# clapclap1386.net
KiCad netlist of a schematic drawn in EAGLE
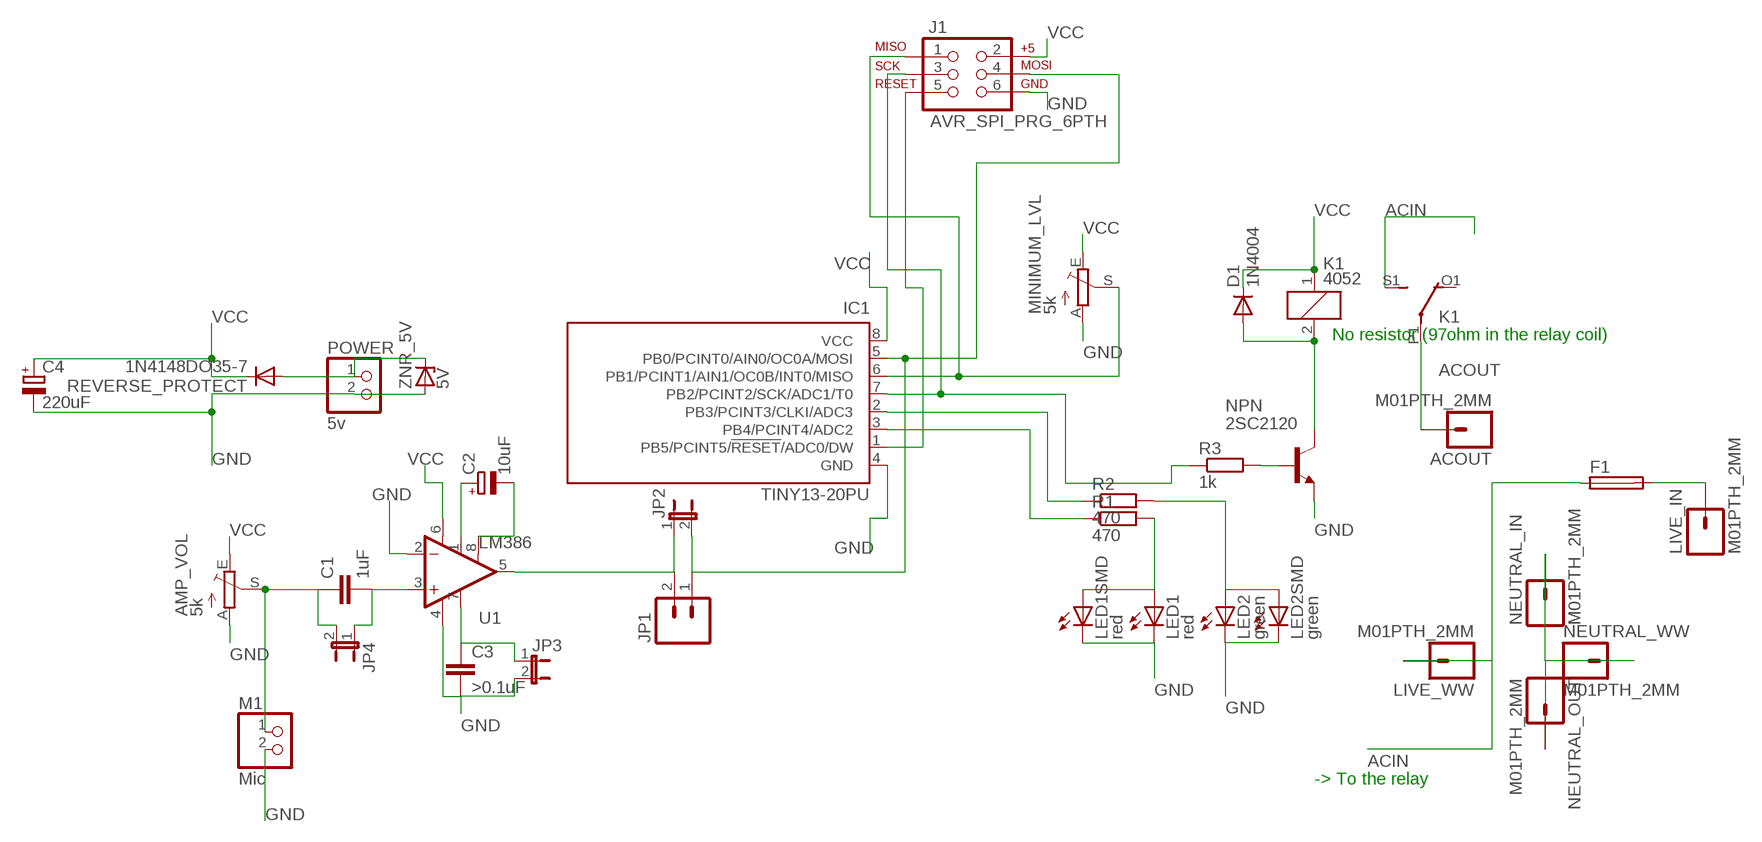
[diagram p0: schematic, sheet 1]

(export (version "E")
  (design (tool "Eeschema 10.0.6"))
  (components
    (comp (ref "ACOUT")
      (value "M01PTH_2MM")
      (footprint "eagle-import:1X01_2MM")
      (libsource (lib "eagle-import") (part "M01PTH_2MM"))
    )
    (comp (ref "AMP_VOL")
      (value "5k")
      (footprint "eagle-import:CT6")
      (libsource (lib "eagle-import") (part "TRIM_EU-CT6"))
    )
    (comp (ref "C1")
      (value "1uF")
      (footprint "eagle-import:C050-024X044")
      (libsource (lib "eagle-import") (part "C-EU050-024X044"))
    )
    (comp (ref "C2")
      (value "10uF")
      (footprint "eagle-import:E2,5-6E")
      (libsource (lib "eagle-import") (part "resistor_CPOL-EUE2,5-6E"))
    )
    (comp (ref "C3")
      (value ">0.1uF")
      (footprint "eagle-import:C025-025X050")
      (libsource (lib "eagle-import") (part "C-EU025-025X050"))
    )
    (comp (ref "C4")
      (value "220uF")
      (footprint "eagle-import:E2,5-6E")
      (libsource (lib "eagle-import") (part "CPOL-EUE2,5-6E"))
    )
    (comp (ref "D1")
      (value "1N4004")
      (footprint "eagle-import:DO41-10")
      (libsource (lib "eagle-import") (part "1N4004"))
    )
    (comp (ref "F1")
      (value "TE5")
      (footprint "eagle-import:TE5")
      (libsource (lib "eagle-import") (part "TE5"))
    )
    (comp (ref "IC1")
      (value "TINY13-20PU")
      (footprint "eagle-import:DIL08")
      (fields (field (name "MPN") "ATTINY13-20PU"))
      (libsource (lib "eagle-import") (part "TINY13PU-20"))
    )
    (comp (ref "J1")
      (value "AVR_SPI_PRG_6PTH")
      (footprint "eagle-import:2X3")
      (libsource (lib "eagle-import") (part "AVR_SPI_PRG_6PTH"))
    )
    (comp (ref "JP1")
      (value "M02PTH")
      (footprint "eagle-import:1X02")
      (libsource (lib "eagle-import") (part "M02PTH"))
    )
    (comp (ref "JP2")
      (value "JUMPER-2SMD-NO")
      (footprint "eagle-import:SJ_2S-NO")
      (libsource (lib "eagle-import") (part "JUMPER-2SMD-NO"))
    )
    (comp (ref "JP3")
      (value "JUMPER-2SMD-NO")
      (footprint "eagle-import:SJ_2S-NO")
      (libsource (lib "eagle-import") (part "JUMPER-2SMD-NO"))
    )
    (comp (ref "JP4")
      (value "JUMPER-2SMD-NO")
      (footprint "eagle-import:SJ_2S-NO")
      (libsource (lib "eagle-import") (part "JUMPER-2SMD-NO"))
    )
    (comp (ref "K1")
      (value "4052")
      (footprint "eagle-import:F4052")
      (libsource (lib "eagle-import") (part "4052"))
    )
    (comp (ref "LED1")
      (value "red")
      (footprint "eagle-import:LED3MM")
      (libsource (lib "eagle-import") (part "LED3MM"))
    )
    (comp (ref "LED1SMD")
      (value "red")
      (footprint "eagle-import:KA-3528ASYC")
      (libsource (lib "eagle-import") (part "LEDKA-3528ASYC"))
    )
    (comp (ref "LED2")
      (value "green")
      (footprint "eagle-import:LED3MM")
      (libsource (lib "eagle-import") (part "LED3MM"))
    )
    (comp (ref "LED2SMD")
      (value "green")
      (footprint "eagle-import:KA-3528ASYC")
      (libsource (lib "eagle-import") (part "LEDKA-3528ASYC"))
    )
    (comp (ref "LIVE_IN")
      (value "M01PTH_2MM")
      (footprint "eagle-import:1X01_2MM")
      (libsource (lib "eagle-import") (part "M01PTH_2MM"))
    )
    (comp (ref "LIVE_WW")
      (value "M01PTH_2MM")
      (footprint "eagle-import:1X01_2MM")
      (libsource (lib "eagle-import") (part "M01PTH_2MM"))
    )
    (comp (ref "M1")
      (value "Mic")
      (footprint "eagle-import:1X02")
      (libsource (lib "eagle-import") (part "PINHD-1X2"))
    )
    (comp (ref "MINIMUM_LVL")
      (value "5k")
      (footprint "eagle-import:CT6")
      (libsource (lib "eagle-import") (part "TRIM_EU-CT6"))
    )
    (comp (ref "NEUTRAL_IN")
      (value "M01PTH_2MM")
      (footprint "eagle-import:1X01_2MM")
      (libsource (lib "eagle-import") (part "M01PTH_2MM"))
    )
    (comp (ref "NEUTRAL_OUT")
      (value "M01PTH_2MM")
      (footprint "eagle-import:1X01_2MM")
      (libsource (lib "eagle-import") (part "M01PTH_2MM"))
    )
    (comp (ref "NEUTRAL_WW")
      (value "M01PTH_2MM")
      (footprint "eagle-import:1X01_2MM")
      (libsource (lib "eagle-import") (part "M01PTH_2MM"))
    )
    (comp (ref "NPN")
      (value "2SC2120")
      (footprint "eagle-import:TO92-ECB")
      (libsource (lib "eagle-import") (part "-NPN-TO92-ECB"))
    )
    (comp (ref "POWER")
      (value "5v")
      (footprint "eagle-import:1X02")
      (libsource (lib "eagle-import") (part "PINHD-1X2"))
    )
    (comp (ref "R1")
      (value "470")
      (footprint "eagle-import:0204V")
      (libsource (lib "eagle-import") (part "R-EU_0204/2V"))
    )
    (comp (ref "R2")
      (value "470")
      (footprint "eagle-import:0204V")
      (libsource (lib "eagle-import") (part "R-EU_0204/2V"))
    )
    (comp (ref "R3")
      (value "1k")
      (footprint "eagle-import:0207_2V")
      (libsource (lib "eagle-import") (part "R-EU_0207/2V"))
    )
    (comp (ref "REVERSE_PROTECT")
      (value "1N4148DO35-7")
      (footprint "eagle-import:DO35-7")
      (libsource (lib "eagle-import") (part "1N4148DO35-7"))
    )
    (comp (ref "U1")
      (value "LM386")
      (footprint "eagle-import:DIP08")
      (libsource (lib "eagle-import") (part "LM386"))
    )
    (comp (ref "ZNR_5V")
      (value "5V")
      (footprint "eagle-import:ZDIO-2.5")
      (libsource (lib "eagle-import") (part "ZENER-DIODEZD-2.5"))
    )
  )
  (nets
    (net (code "1") (name "/ACIN") (class "Default")
      (node (ref "F1") (pin "1") (pinfunction "1_1") (pintype "passive"))
      (node (ref "K1") (pin "S1") (pinfunction "S_S1") (pintype "passive"))
      (node (ref "LIVE_WW") (pin "1") (pinfunction "1_1") (pintype "passive"))
    )
    (net (code "2") (name "/ACOUT") (class "Default")
      (node (ref "ACOUT") (pin "1") (pinfunction "1_1") (pintype "passive"))
      (node (ref "K1") (pin "P1") (pinfunction "P_P1") (pintype "passive"))
    )
    (net (code "3") (name "/GND") (class "Default")
      (node (ref "AMP_VOL") (pin "A") (pinfunction "A_A") (pintype "passive"))
      (node (ref "C3") (pin "2") (pinfunction "2_2") (pintype "passive"))
      (node (ref "C4") (pin "-") (pinfunction "-_-") (pintype "passive"))
      (node (ref "IC1") (pin "4") (pinfunction "GND_4") (pintype "power_in"))
      (node (ref "J1") (pin "6") (pinfunction "6_6") (pintype "passive"))
      (node (ref "JP3") (pin "2") (pinfunction "2_2") (pintype "passive"))
      (node (ref "LED1") (pin "K") (pinfunction "C_K") (pintype "passive"))
      (node (ref "LED1SMD") (pin "C") (pinfunction "C_C") (pintype "passive"))
      (node (ref "LED2") (pin "K") (pinfunction "C_K") (pintype "passive"))
      (node (ref "LED2SMD") (pin "C") (pinfunction "C_C") (pintype "passive"))
      (node (ref "M1") (pin "2") (pinfunction "2_2") (pintype "passive"))
      (node (ref "MINIMUM_LVL") (pin "A") (pinfunction "A_A") (pintype "passive"))
      (node (ref "NPN") (pin "E") (pinfunction "E_E") (pintype "passive"))
      (node (ref "POWER") (pin "2") (pinfunction "2_2") (pintype "passive"))
      (node (ref "U1") (pin "2") (pinfunction "-IN_2") (pintype "input"))
      (node (ref "U1") (pin "4") (pinfunction "V-_4") (pintype "power_in"))
      (node (ref "ZNR_5V") (pin "A") (pinfunction "A_A") (pintype "passive"))
    )
    (net (code "4") (name "/VCC") (class "Default")
      (node (ref "AMP_VOL") (pin "E") (pinfunction "E_E") (pintype "passive"))
      (node (ref "C4") (pin "+") (pinfunction "+_+") (pintype "passive"))
      (node (ref "D1") (pin "C") (pinfunction "C_C") (pintype "passive"))
      (node (ref "IC1") (pin "8") (pinfunction "VCC_8") (pintype "power_in"))
      (node (ref "J1") (pin "2") (pinfunction "2_2") (pintype "passive"))
      (node (ref "K1") (pin "1") (pinfunction "1_1") (pintype "passive"))
      (node (ref "MINIMUM_LVL") (pin "E") (pinfunction "E_E") (pintype "passive"))
      (node (ref "REVERSE_PROTECT") (pin "C") (pinfunction "C_C") (pintype "passive"))
      (node (ref "U1") (pin "6") (pinfunction "V+_6") (pintype "power_in"))
    )
    (net (code "5") (name "Net-(AMP_VOL-PadS)") (class "Default")
      (node (ref "AMP_VOL") (pin "S") (pinfunction "S_S") (pintype "passive"))
      (node (ref "C1") (pin "1") (pinfunction "1_1") (pintype "passive"))
      (node (ref "JP4") (pin "2") (pinfunction "2_2") (pintype "passive"))
      (node (ref "M1") (pin "1") (pinfunction "1_1") (pintype "passive"))
    )
    (net (code "6") (name "Net-(C2-Pad+)") (class "Default")
      (node (ref "C2") (pin "+") (pinfunction "+_+") (pintype "passive"))
      (node (ref "U1") (pin "1") (pinfunction "GAIN_1") (pintype "bidirectional"))
    )
    (net (code "7") (name "Net-(C2-Pad-)") (class "Default")
      (node (ref "C2") (pin "-") (pinfunction "-_-") (pintype "passive"))
      (node (ref "U1") (pin "8") (pinfunction "GAIN_8") (pintype "bidirectional"))
    )
    (net (code "8") (name "Net-(D1-PadA)") (class "Default")
      (node (ref "D1") (pin "A") (pinfunction "A_A") (pintype "passive"))
      (node (ref "K1") (pin "2") (pinfunction "2_2") (pintype "passive"))
      (node (ref "NPN") (pin "C") (pinfunction "C_C") (pintype "passive"))
    )
    (net (code "9") (name "Net-(F1-Pad2)") (class "Default")
      (node (ref "F1") (pin "2") (pinfunction "2_2") (pintype "passive"))
      (node (ref "LIVE_IN") (pin "1") (pinfunction "1_1") (pintype "passive"))
    )
    (net (code "10") (name "Net-(IC1-PB0{slash}PCINT0{slash}AIN0{slash}OC0A{slash}MOSI)") (class "Default")
      (node (ref "IC1") (pin "5") (pinfunction "PB0/PCINT0/AIN0/OC0A/MOSI_5") (pintype "bidirectional"))
      (node (ref "J1") (pin "4") (pinfunction "4_4") (pintype "passive"))
      (node (ref "JP1") (pin "1") (pinfunction "1_1") (pintype "passive"))
      (node (ref "JP2") (pin "2") (pinfunction "2_2") (pintype "passive"))
    )
    (net (code "11") (name "Net-(IC1-PB1{slash}PCINT1{slash}AIN1{slash}OC0B{slash}INT0{slash}MISO)") (class "Default")
      (node (ref "IC1") (pin "6") (pinfunction "PB1/PCINT1/AIN1/OC0B/INT0/MISO_6") (pintype "bidirectional"))
      (node (ref "J1") (pin "1") (pinfunction "1_1") (pintype "passive"))
      (node (ref "MINIMUM_LVL") (pin "S") (pinfunction "S_S") (pintype "passive"))
    )
    (net (code "12") (name "Net-(IC1-PB2{slash}PCINT2{slash}SCK{slash}ADC1{slash}T0)") (class "Default")
      (node (ref "IC1") (pin "7") (pinfunction "PB2/PCINT2/SCK/ADC1/T0_7") (pintype "bidirectional"))
      (node (ref "J1") (pin "3") (pinfunction "3_3") (pintype "passive"))
      (node (ref "R3") (pin "1") (pinfunction "1_1") (pintype "passive"))
    )
    (net (code "13") (name "Net-(IC1-PB3{slash}PCINT3{slash}CLKI{slash}ADC3)") (class "Default")
      (node (ref "IC1") (pin "2") (pinfunction "PB3/PCINT3/CLKI/ADC3_2") (pintype "bidirectional"))
      (node (ref "R2") (pin "1") (pinfunction "1_1") (pintype "passive"))
    )
    (net (code "14") (name "Net-(IC1-PB4{slash}PCINT4{slash}ADC2)") (class "Default")
      (node (ref "IC1") (pin "3") (pinfunction "PB4/PCINT4/ADC2_3") (pintype "bidirectional"))
      (node (ref "R1") (pin "1") (pinfunction "1_1") (pintype "passive"))
    )
    (net (code "15") (name "Net-(IC1-PB5{slash}PCINT5{slash}~{RESET}{slash}ADC0{slash}DW)") (class "Default")
      (node (ref "IC1") (pin "1") (pinfunction "PB5/PCINT5/~{RESET}/ADC0/DW_1") (pintype "bidirectional"))
      (node (ref "J1") (pin "5") (pinfunction "5_5") (pintype "passive"))
    )
    (net (code "16") (name "Net-(LED1-PadA)") (class "Default")
      (node (ref "LED1") (pin "A") (pinfunction "A_A") (pintype "passive"))
      (node (ref "LED1SMD") (pin "A") (pinfunction "A_A") (pintype "passive"))
      (node (ref "R1") (pin "2") (pinfunction "2_2") (pintype "passive"))
    )
    (net (code "17") (name "Net-(LED2-PadA)") (class "Default")
      (node (ref "LED2") (pin "A") (pinfunction "A_A") (pintype "passive"))
      (node (ref "LED2SMD") (pin "A") (pinfunction "A_A") (pintype "passive"))
      (node (ref "R2") (pin "2") (pinfunction "2_2") (pintype "passive"))
    )
    (net (code "18") (name "Net-(NEUTRAL_IN-Pad1)") (class "Default")
      (node (ref "NEUTRAL_IN") (pin "1") (pinfunction "1_1") (pintype "passive"))
      (node (ref "NEUTRAL_OUT") (pin "1") (pinfunction "1_1") (pintype "passive"))
      (node (ref "NEUTRAL_WW") (pin "1") (pinfunction "1_1") (pintype "passive"))
    )
    (net (code "19") (name "Net-(NPN-PadB)") (class "Default")
      (node (ref "NPN") (pin "B") (pinfunction "B_B") (pintype "passive"))
      (node (ref "R3") (pin "2") (pinfunction "2_2") (pintype "passive"))
    )
    (net (code "20") (name "Net-(POWER-Pad1)") (class "Default")
      (node (ref "POWER") (pin "1") (pinfunction "1_1") (pintype "passive"))
      (node (ref "REVERSE_PROTECT") (pin "A") (pinfunction "A_A") (pintype "passive"))
      (node (ref "ZNR_5V") (pin "C") (pinfunction "C_C") (pintype "passive"))
    )
    (net (code "21") (name "Net-(U1-+IN)") (class "Default")
      (node (ref "C1") (pin "2") (pinfunction "2_2") (pintype "passive"))
      (node (ref "JP4") (pin "1") (pinfunction "1_1") (pintype "passive"))
      (node (ref "U1") (pin "3") (pinfunction "+IN_3") (pintype "input"))
    )
    (net (code "22") (name "Net-(U1-BP)") (class "Default")
      (node (ref "C3") (pin "1") (pinfunction "1_1") (pintype "passive"))
      (node (ref "JP3") (pin "1") (pinfunction "1_1") (pintype "passive"))
      (node (ref "U1") (pin "7") (pinfunction "BP_7") (pintype "bidirectional"))
    )
    (net (code "23") (name "Net-(U1-OUT)") (class "Default")
      (node (ref "JP1") (pin "2") (pinfunction "2_2") (pintype "passive"))
      (node (ref "JP2") (pin "1") (pinfunction "1_1") (pintype "passive"))
      (node (ref "U1") (pin "5") (pinfunction "OUT_5") (pintype "output"))
    )
    (net (code "24") (name "unconnected-(K1B-O-PadO1)") (class "Default")
      (node (ref "K1") (pin "O1") (pinfunction "O_O1") (pintype "passive"))
    )
  )
)
